# Gelijkrichter.net
KiCad netlist of a schematic drawn in EAGLE
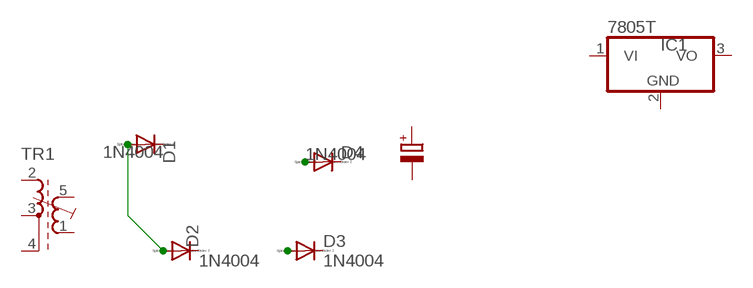
[diagram p0: schematic, sheet 1]

(export (version "E")
  (design (tool "Eeschema 10.0.6"))
  (components
    (comp (ref "D1")
      (value "1N4004")
      (footprint "eagle-import:DO41-10")
      (libsource (lib "eagle-import") (part "1N4004"))
    )
    (comp (ref "D2")
      (value "1N4004")
      (footprint "eagle-import:DO41-10")
      (libsource (lib "eagle-import") (part "1N4004"))
    )
    (comp (ref "D3")
      (value "1N4004")
      (footprint "eagle-import:DO41-10")
      (libsource (lib "eagle-import") (part "1N4004"))
    )
    (comp (ref "D4")
      (value "1N4004")
      (footprint "eagle-import:DO41-10")
      (libsource (lib "eagle-import") (part "1N4004"))
    )
    (comp (ref "IC1")
      (value "7805T")
      (footprint "eagle-import:TO220H")
      (libsource (lib "eagle-import") (part "78T05"))
    )
    (comp (ref "TR1")
      (value "71-24513-2")
      (footprint "eagle-import:71-5")
      (libsource (lib "eagle-import") (part "71-24513-2"))
    )
  )
  (nets
    (net (code "1") (name "Net-(D1-PadA)") (class "Default")
      (node (ref "D1") (pin "A") (pinfunction "A_A") (pintype "passive"))
      (node (ref "D2") (pin "A") (pinfunction "A_A") (pintype "passive"))
    )
    (net (code "2") (name "unconnected-(D1-PadC)") (class "Default")
      (node (ref "D1") (pin "C") (pinfunction "C_C") (pintype "passive"))
    )
    (net (code "3") (name "unconnected-(D2-PadC)") (class "Default")
      (node (ref "D2") (pin "C") (pinfunction "C_C") (pintype "passive"))
    )
    (net (code "4") (name "unconnected-(D3-PadA)") (class "Default")
      (node (ref "D3") (pin "A") (pinfunction "A_A") (pintype "passive"))
    )
    (net (code "5") (name "unconnected-(D3-PadC)") (class "Default")
      (node (ref "D3") (pin "C") (pinfunction "C_C") (pintype "passive"))
    )
    (net (code "6") (name "unconnected-(D4-PadA)") (class "Default")
      (node (ref "D4") (pin "A") (pinfunction "A_A") (pintype "passive"))
    )
    (net (code "7") (name "unconnected-(D4-PadC)") (class "Default")
      (node (ref "D4") (pin "C") (pinfunction "C_C") (pintype "passive"))
    )
    (net (code "8") (name "unconnected-(IC1-GND-Pad2)") (class "Default")
      (node (ref "IC1") (pin "2") (pinfunction "GND_2") (pintype "passive"))
    )
    (net (code "9") (name "unconnected-(IC1-VI-Pad1)") (class "Default")
      (node (ref "IC1") (pin "1") (pinfunction "VI_1") (pintype "input"))
    )
    (net (code "10") (name "unconnected-(IC1-VO-Pad3)") (class "Default")
      (node (ref "IC1") (pin "3") (pinfunction "VO_3") (pintype "passive"))
    )
    (net (code "11") (name "unconnected-(TR1A-A1-Pad2)") (class "Default")
      (node (ref "TR1") (pin "2") (pinfunction "A1_2") (pintype "passive"))
    )
    (net (code "12") (name "unconnected-(TR1A-A2-Pad5)") (class "Default")
      (node (ref "TR1") (pin "5") (pinfunction "A2_5") (pintype "passive"))
    )
    (net (code "13") (name "unconnected-(TR1A-E1-Pad4)") (class "Default")
      (node (ref "TR1") (pin "4") (pinfunction "E1_4") (pintype "passive"))
    )
    (net (code "14") (name "unconnected-(TR1A-E2-Pad1)") (class "Default")
      (node (ref "TR1") (pin "1") (pinfunction "E2_1") (pintype "passive"))
    )
    (net (code "15") (name "unconnected-(TR1A-Z-Pad3)") (class "Default")
      (node (ref "TR1") (pin "3") (pinfunction "Z_3") (pintype "passive"))
    )
  )
)
